# 8x8_led_matrix.net
KiCad netlist of a schematic drawn in EAGLE
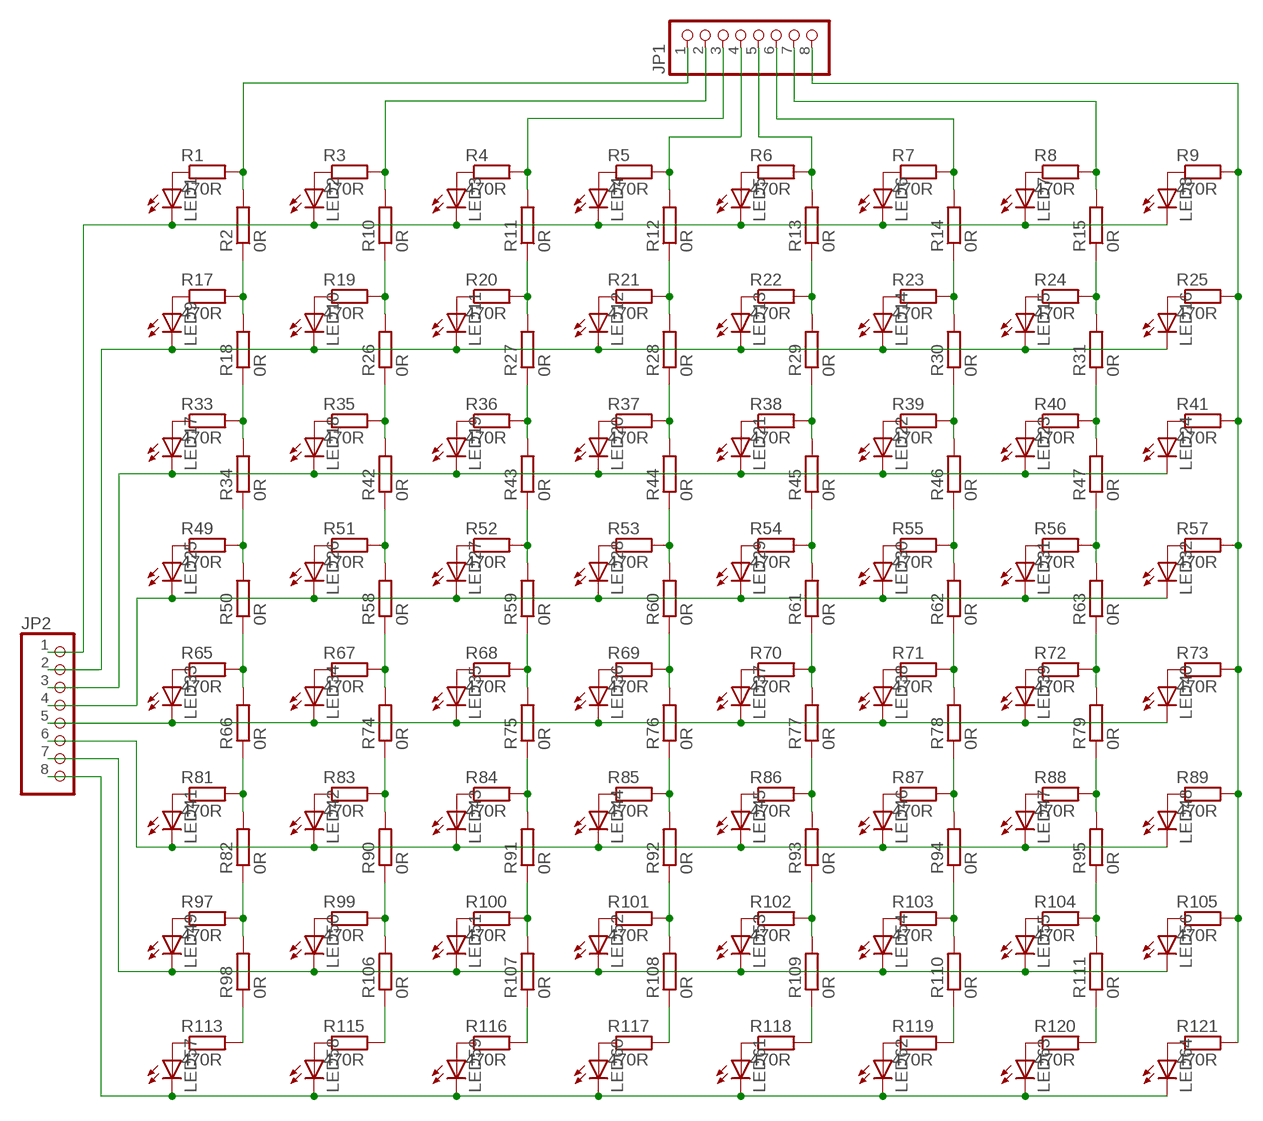
[diagram p0: schematic, sheet 1]

(export (version "E")
  (design (tool "Eeschema 10.0.6"))
  (components
    (comp (ref "JP1")
      (value "PINHD-1X8")
      (footprint "eagle-import:1X08")
      (libsource (lib "eagle-import") (part "PINHD-1X8"))
    )
    (comp (ref "JP2")
      (value "PINHD-1X8")
      (footprint "eagle-import:1X08")
      (libsource (lib "eagle-import") (part "PINHD-1X8"))
    )
    (comp (ref "LED1")
      (value "LED5MM")
      (footprint "eagle-import:LED5MM")
      (libsource (lib "eagle-import") (part "LED5MM"))
    )
    (comp (ref "LED2")
      (value "LED5MM")
      (footprint "eagle-import:LED5MM")
      (libsource (lib "eagle-import") (part "LED5MM"))
    )
    (comp (ref "LED3")
      (value "LED5MM")
      (footprint "eagle-import:LED5MM")
      (libsource (lib "eagle-import") (part "LED5MM"))
    )
    (comp (ref "LED4")
      (value "LED5MM")
      (footprint "eagle-import:LED5MM")
      (libsource (lib "eagle-import") (part "LED5MM"))
    )
    (comp (ref "LED5")
      (value "LED5MM")
      (footprint "eagle-import:LED5MM")
      (libsource (lib "eagle-import") (part "LED5MM"))
    )
    (comp (ref "LED6")
      (value "LED5MM")
      (footprint "eagle-import:LED5MM")
      (libsource (lib "eagle-import") (part "LED5MM"))
    )
    (comp (ref "LED7")
      (value "LED5MM")
      (footprint "eagle-import:LED5MM")
      (libsource (lib "eagle-import") (part "LED5MM"))
    )
    (comp (ref "LED8")
      (value "LED5MM")
      (footprint "eagle-import:LED5MM")
      (libsource (lib "eagle-import") (part "LED5MM"))
    )
    (comp (ref "LED9")
      (value "LED5MM")
      (footprint "eagle-import:LED5MM")
      (libsource (lib "eagle-import") (part "LED5MM"))
    )
    (comp (ref "LED10")
      (value "LED5MM")
      (footprint "eagle-import:LED5MM")
      (libsource (lib "eagle-import") (part "LED5MM"))
    )
    (comp (ref "LED11")
      (value "LED5MM")
      (footprint "eagle-import:LED5MM")
      (libsource (lib "eagle-import") (part "LED5MM"))
    )
    (comp (ref "LED12")
      (value "LED5MM")
      (footprint "eagle-import:LED5MM")
      (libsource (lib "eagle-import") (part "LED5MM"))
    )
    (comp (ref "LED13")
      (value "LED5MM")
      (footprint "eagle-import:LED5MM")
      (libsource (lib "eagle-import") (part "LED5MM"))
    )
    (comp (ref "LED14")
      (value "LED5MM")
      (footprint "eagle-import:LED5MM")
      (libsource (lib "eagle-import") (part "LED5MM"))
    )
    (comp (ref "LED15")
      (value "LED5MM")
      (footprint "eagle-import:LED5MM")
      (libsource (lib "eagle-import") (part "LED5MM"))
    )
    (comp (ref "LED16")
      (value "LED5MM")
      (footprint "eagle-import:LED5MM")
      (libsource (lib "eagle-import") (part "LED5MM"))
    )
    (comp (ref "LED17")
      (value "LED5MM")
      (footprint "eagle-import:LED5MM")
      (libsource (lib "eagle-import") (part "LED5MM"))
    )
    (comp (ref "LED18")
      (value "LED5MM")
      (footprint "eagle-import:LED5MM")
      (libsource (lib "eagle-import") (part "LED5MM"))
    )
    (comp (ref "LED19")
      (value "LED5MM")
      (footprint "eagle-import:LED5MM")
      (libsource (lib "eagle-import") (part "LED5MM"))
    )
    (comp (ref "LED20")
      (value "LED5MM")
      (footprint "eagle-import:LED5MM")
      (libsource (lib "eagle-import") (part "LED5MM"))
    )
    (comp (ref "LED21")
      (value "LED5MM")
      (footprint "eagle-import:LED5MM")
      (libsource (lib "eagle-import") (part "LED5MM"))
    )
    (comp (ref "LED22")
      (value "LED5MM")
      (footprint "eagle-import:LED5MM")
      (libsource (lib "eagle-import") (part "LED5MM"))
    )
    (comp (ref "LED23")
      (value "LED5MM")
      (footprint "eagle-import:LED5MM")
      (libsource (lib "eagle-import") (part "LED5MM"))
    )
    (comp (ref "LED24")
      (value "LED5MM")
      (footprint "eagle-import:LED5MM")
      (libsource (lib "eagle-import") (part "LED5MM"))
    )
    (comp (ref "LED25")
      (value "LED5MM")
      (footprint "eagle-import:LED5MM")
      (libsource (lib "eagle-import") (part "LED5MM"))
    )
    (comp (ref "LED26")
      (value "LED5MM")
      (footprint "eagle-import:LED5MM")
      (libsource (lib "eagle-import") (part "LED5MM"))
    )
    (comp (ref "LED27")
      (value "LED5MM")
      (footprint "eagle-import:LED5MM")
      (libsource (lib "eagle-import") (part "LED5MM"))
    )
    (comp (ref "LED28")
      (value "LED5MM")
      (footprint "eagle-import:LED5MM")
      (libsource (lib "eagle-import") (part "LED5MM"))
    )
    (comp (ref "LED29")
      (value "LED5MM")
      (footprint "eagle-import:LED5MM")
      (libsource (lib "eagle-import") (part "LED5MM"))
    )
    (comp (ref "LED30")
      (value "LED5MM")
      (footprint "eagle-import:LED5MM")
      (libsource (lib "eagle-import") (part "LED5MM"))
    )
    (comp (ref "LED31")
      (value "LED5MM")
      (footprint "eagle-import:LED5MM")
      (libsource (lib "eagle-import") (part "LED5MM"))
    )
    (comp (ref "LED32")
      (value "LED5MM")
      (footprint "eagle-import:LED5MM")
      (libsource (lib "eagle-import") (part "LED5MM"))
    )
    (comp (ref "LED33")
      (value "LED5MM")
      (footprint "eagle-import:LED5MM")
      (libsource (lib "eagle-import") (part "LED5MM"))
    )
    (comp (ref "LED34")
      (value "LED5MM")
      (footprint "eagle-import:LED5MM")
      (libsource (lib "eagle-import") (part "LED5MM"))
    )
    (comp (ref "LED35")
      (value "LED5MM")
      (footprint "eagle-import:LED5MM")
      (libsource (lib "eagle-import") (part "LED5MM"))
    )
    (comp (ref "LED36")
      (value "LED5MM")
      (footprint "eagle-import:LED5MM")
      (libsource (lib "eagle-import") (part "LED5MM"))
    )
    (comp (ref "LED37")
      (value "LED5MM")
      (footprint "eagle-import:LED5MM")
      (libsource (lib "eagle-import") (part "LED5MM"))
    )
    (comp (ref "LED38")
      (value "LED5MM")
      (footprint "eagle-import:LED5MM")
      (libsource (lib "eagle-import") (part "LED5MM"))
    )
    (comp (ref "LED39")
      (value "LED5MM")
      (footprint "eagle-import:LED5MM")
      (libsource (lib "eagle-import") (part "LED5MM"))
    )
    (comp (ref "LED40")
      (value "LED5MM")
      (footprint "eagle-import:LED5MM")
      (libsource (lib "eagle-import") (part "LED5MM"))
    )
    (comp (ref "LED41")
      (value "LED5MM")
      (footprint "eagle-import:LED5MM")
      (libsource (lib "eagle-import") (part "LED5MM"))
    )
    (comp (ref "LED42")
      (value "LED5MM")
      (footprint "eagle-import:LED5MM")
      (libsource (lib "eagle-import") (part "LED5MM"))
    )
    (comp (ref "LED43")
      (value "LED5MM")
      (footprint "eagle-import:LED5MM")
      (libsource (lib "eagle-import") (part "LED5MM"))
    )
    (comp (ref "LED44")
      (value "LED5MM")
      (footprint "eagle-import:LED5MM")
      (libsource (lib "eagle-import") (part "LED5MM"))
    )
    (comp (ref "LED45")
      (value "LED5MM")
      (footprint "eagle-import:LED5MM")
      (libsource (lib "eagle-import") (part "LED5MM"))
    )
    (comp (ref "LED46")
      (value "LED5MM")
      (footprint "eagle-import:LED5MM")
      (libsource (lib "eagle-import") (part "LED5MM"))
    )
    (comp (ref "LED47")
      (value "LED5MM")
      (footprint "eagle-import:LED5MM")
      (libsource (lib "eagle-import") (part "LED5MM"))
    )
    (comp (ref "LED48")
      (value "LED5MM")
      (footprint "eagle-import:LED5MM")
      (libsource (lib "eagle-import") (part "LED5MM"))
    )
    (comp (ref "LED49")
      (value "LED5MM")
      (footprint "eagle-import:LED5MM")
      (libsource (lib "eagle-import") (part "LED5MM"))
    )
    (comp (ref "LED50")
      (value "LED5MM")
      (footprint "eagle-import:LED5MM")
      (libsource (lib "eagle-import") (part "LED5MM"))
    )
    (comp (ref "LED51")
      (value "LED5MM")
      (footprint "eagle-import:LED5MM")
      (libsource (lib "eagle-import") (part "LED5MM"))
    )
    (comp (ref "LED52")
      (value "LED5MM")
      (footprint "eagle-import:LED5MM")
      (libsource (lib "eagle-import") (part "LED5MM"))
    )
    (comp (ref "LED53")
      (value "LED5MM")
      (footprint "eagle-import:LED5MM")
      (libsource (lib "eagle-import") (part "LED5MM"))
    )
    (comp (ref "LED54")
      (value "LED5MM")
      (footprint "eagle-import:LED5MM")
      (libsource (lib "eagle-import") (part "LED5MM"))
    )
    (comp (ref "LED55")
      (value "LED5MM")
      (footprint "eagle-import:LED5MM")
      (libsource (lib "eagle-import") (part "LED5MM"))
    )
    (comp (ref "LED56")
      (value "LED5MM")
      (footprint "eagle-import:LED5MM")
      (libsource (lib "eagle-import") (part "LED5MM"))
    )
    (comp (ref "LED57")
      (value "LED5MM")
      (footprint "eagle-import:LED5MM")
      (libsource (lib "eagle-import") (part "LED5MM"))
    )
    (comp (ref "LED58")
      (value "LED5MM")
      (footprint "eagle-import:LED5MM")
      (libsource (lib "eagle-import") (part "LED5MM"))
    )
    (comp (ref "LED59")
      (value "LED5MM")
      (footprint "eagle-import:LED5MM")
      (libsource (lib "eagle-import") (part "LED5MM"))
    )
    (comp (ref "LED60")
      (value "LED5MM")
      (footprint "eagle-import:LED5MM")
      (libsource (lib "eagle-import") (part "LED5MM"))
    )
    (comp (ref "LED61")
      (value "LED5MM")
      (footprint "eagle-import:LED5MM")
      (libsource (lib "eagle-import") (part "LED5MM"))
    )
    (comp (ref "LED62")
      (value "LED5MM")
      (footprint "eagle-import:LED5MM")
      (libsource (lib "eagle-import") (part "LED5MM"))
    )
    (comp (ref "LED63")
      (value "LED5MM")
      (footprint "eagle-import:LED5MM")
      (libsource (lib "eagle-import") (part "LED5MM"))
    )
    (comp (ref "LED64")
      (value "LED5MM")
      (footprint "eagle-import:LED5MM")
      (libsource (lib "eagle-import") (part "LED5MM"))
    )
    (comp (ref "R1")
      (value "470R")
      (footprint "eagle-import:R0603")
      (libsource (lib "eagle-import") (part "R-EU_R0603"))
    )
    (comp (ref "R2")
      (value "0R")
      (footprint "eagle-import:R1206")
      (libsource (lib "eagle-import") (part "R-EU_R1206"))
    )
    (comp (ref "R3")
      (value "470R")
      (footprint "eagle-import:R0603")
      (libsource (lib "eagle-import") (part "R-EU_R0603"))
    )
    (comp (ref "R4")
      (value "470R")
      (footprint "eagle-import:R0603")
      (libsource (lib "eagle-import") (part "R-EU_R0603"))
    )
    (comp (ref "R5")
      (value "470R")
      (footprint "eagle-import:R0603")
      (libsource (lib "eagle-import") (part "R-EU_R0603"))
    )
    (comp (ref "R6")
      (value "470R")
      (footprint "eagle-import:R0603")
      (libsource (lib "eagle-import") (part "R-EU_R0603"))
    )
    (comp (ref "R7")
      (value "470R")
      (footprint "eagle-import:R0603")
      (libsource (lib "eagle-import") (part "R-EU_R0603"))
    )
    (comp (ref "R8")
      (value "470R")
      (footprint "eagle-import:R0603")
      (libsource (lib "eagle-import") (part "R-EU_R0603"))
    )
    (comp (ref "R9")
      (value "470R")
      (footprint "eagle-import:R0603")
      (libsource (lib "eagle-import") (part "R-EU_R0603"))
    )
    (comp (ref "R10")
      (value "0R")
      (footprint "eagle-import:R1206")
      (libsource (lib "eagle-import") (part "R-EU_R1206"))
    )
    (comp (ref "R11")
      (value "0R")
      (footprint "eagle-import:R1206")
      (libsource (lib "eagle-import") (part "R-EU_R1206"))
    )
    (comp (ref "R12")
      (value "0R")
      (footprint "eagle-import:R1206")
      (libsource (lib "eagle-import") (part "R-EU_R1206"))
    )
    (comp (ref "R13")
      (value "0R")
      (footprint "eagle-import:R1206")
      (libsource (lib "eagle-import") (part "R-EU_R1206"))
    )
    (comp (ref "R14")
      (value "0R")
      (footprint "eagle-import:R1206")
      (libsource (lib "eagle-import") (part "R-EU_R1206"))
    )
    (comp (ref "R15")
      (value "0R")
      (footprint "eagle-import:R1206")
      (libsource (lib "eagle-import") (part "R-EU_R1206"))
    )
    (comp (ref "R17")
      (value "470R")
      (footprint "eagle-import:R0603")
      (libsource (lib "eagle-import") (part "R-EU_R0603"))
    )
    (comp (ref "R18")
      (value "0R")
      (footprint "eagle-import:R1206")
      (libsource (lib "eagle-import") (part "R-EU_R1206"))
    )
    (comp (ref "R19")
      (value "470R")
      (footprint "eagle-import:R0603")
      (libsource (lib "eagle-import") (part "R-EU_R0603"))
    )
    (comp (ref "R20")
      (value "470R")
      (footprint "eagle-import:R0603")
      (libsource (lib "eagle-import") (part "R-EU_R0603"))
    )
    (comp (ref "R21")
      (value "470R")
      (footprint "eagle-import:R0603")
      (libsource (lib "eagle-import") (part "R-EU_R0603"))
    )
    (comp (ref "R22")
      (value "470R")
      (footprint "eagle-import:R0603")
      (libsource (lib "eagle-import") (part "R-EU_R0603"))
    )
    (comp (ref "R23")
      (value "470R")
      (footprint "eagle-import:R0603")
      (libsource (lib "eagle-import") (part "R-EU_R0603"))
    )
    (comp (ref "R24")
      (value "470R")
      (footprint "eagle-import:R0603")
      (libsource (lib "eagle-import") (part "R-EU_R0603"))
    )
    (comp (ref "R25")
      (value "470R")
      (footprint "eagle-import:R0603")
      (libsource (lib "eagle-import") (part "R-EU_R0603"))
    )
    (comp (ref "R26")
      (value "0R")
      (footprint "eagle-import:R1206")
      (libsource (lib "eagle-import") (part "R-EU_R1206"))
    )
    (comp (ref "R27")
      (value "0R")
      (footprint "eagle-import:R1206")
      (libsource (lib "eagle-import") (part "R-EU_R1206"))
    )
    (comp (ref "R28")
      (value "0R")
      (footprint "eagle-import:R1206")
      (libsource (lib "eagle-import") (part "R-EU_R1206"))
    )
    (comp (ref "R29")
      (value "0R")
      (footprint "eagle-import:R1206")
      (libsource (lib "eagle-import") (part "R-EU_R1206"))
    )
    (comp (ref "R30")
      (value "0R")
      (footprint "eagle-import:R1206")
      (libsource (lib "eagle-import") (part "R-EU_R1206"))
    )
    (comp (ref "R31")
      (value "0R")
      (footprint "eagle-import:R1206")
      (libsource (lib "eagle-import") (part "R-EU_R1206"))
    )
    (comp (ref "R33")
      (value "470R")
      (footprint "eagle-import:R0603")
      (libsource (lib "eagle-import") (part "R-EU_R0603"))
    )
    (comp (ref "R34")
      (value "0R")
      (footprint "eagle-import:R1206")
      (libsource (lib "eagle-import") (part "R-EU_R1206"))
    )
    (comp (ref "R35")
      (value "470R")
      (footprint "eagle-import:R0603")
      (libsource (lib "eagle-import") (part "R-EU_R0603"))
    )
    (comp (ref "R36")
      (value "470R")
      (footprint "eagle-import:R0603")
      (libsource (lib "eagle-import") (part "R-EU_R0603"))
    )
    (comp (ref "R37")
      (value "470R")
      (footprint "eagle-import:R0603")
      (libsource (lib "eagle-import") (part "R-EU_R0603"))
    )
    (comp (ref "R38")
      (value "470R")
      (footprint "eagle-import:R0603")
      (libsource (lib "eagle-import") (part "R-EU_R0603"))
    )
    (comp (ref "R39")
      (value "470R")
      (footprint "eagle-import:R0603")
      (libsource (lib "eagle-import") (part "R-EU_R0603"))
    )
    (comp (ref "R40")
      (value "470R")
      (footprint "eagle-import:R0603")
      (libsource (lib "eagle-import") (part "R-EU_R0603"))
    )
    (comp (ref "R41")
      (value "470R")
      (footprint "eagle-import:R0603")
      (libsource (lib "eagle-import") (part "R-EU_R0603"))
    )
    (comp (ref "R42")
      (value "0R")
      (footprint "eagle-import:R1206")
      (libsource (lib "eagle-import") (part "R-EU_R1206"))
    )
    (comp (ref "R43")
      (value "0R")
      (footprint "eagle-import:R1206")
      (libsource (lib "eagle-import") (part "R-EU_R1206"))
    )
    (comp (ref "R44")
      (value "0R")
      (footprint "eagle-import:R1206")
      (libsource (lib "eagle-import") (part "R-EU_R1206"))
    )
    (comp (ref "R45")
      (value "0R")
      (footprint "eagle-import:R1206")
      (libsource (lib "eagle-import") (part "R-EU_R1206"))
    )
    (comp (ref "R46")
      (value "0R")
      (footprint "eagle-import:R1206")
      (libsource (lib "eagle-import") (part "R-EU_R1206"))
    )
    (comp (ref "R47")
      (value "0R")
      (footprint "eagle-import:R1206")
      (libsource (lib "eagle-import") (part "R-EU_R1206"))
    )
    (comp (ref "R49")
      (value "470R")
      (footprint "eagle-import:R0603")
      (libsource (lib "eagle-import") (part "R-EU_R0603"))
    )
    (comp (ref "R50")
      (value "0R")
      (footprint "eagle-import:R1206")
      (libsource (lib "eagle-import") (part "R-EU_R1206"))
    )
    (comp (ref "R51")
      (value "470R")
      (footprint "eagle-import:R0603")
      (libsource (lib "eagle-import") (part "R-EU_R0603"))
    )
    (comp (ref "R52")
      (value "470R")
      (footprint "eagle-import:R0603")
      (libsource (lib "eagle-import") (part "R-EU_R0603"))
    )
    (comp (ref "R53")
      (value "470R")
      (footprint "eagle-import:R0603")
      (libsource (lib "eagle-import") (part "R-EU_R0603"))
    )
    (comp (ref "R54")
      (value "470R")
      (footprint "eagle-import:R0603")
      (libsource (lib "eagle-import") (part "R-EU_R0603"))
    )
    (comp (ref "R55")
      (value "470R")
      (footprint "eagle-import:R0603")
      (libsource (lib "eagle-import") (part "R-EU_R0603"))
    )
    (comp (ref "R56")
      (value "470R")
      (footprint "eagle-import:R0603")
      (libsource (lib "eagle-import") (part "R-EU_R0603"))
    )
    (comp (ref "R57")
      (value "470R")
      (footprint "eagle-import:R0603")
      (libsource (lib "eagle-import") (part "R-EU_R0603"))
    )
    (comp (ref "R58")
      (value "0R")
      (footprint "eagle-import:R1206")
      (libsource (lib "eagle-import") (part "R-EU_R1206"))
    )
    (comp (ref "R59")
      (value "0R")
      (footprint "eagle-import:R1206")
      (libsource (lib "eagle-import") (part "R-EU_R1206"))
    )
    (comp (ref "R60")
      (value "0R")
      (footprint "eagle-import:R1206")
      (libsource (lib "eagle-import") (part "R-EU_R1206"))
    )
    (comp (ref "R61")
      (value "0R")
      (footprint "eagle-import:R1206")
      (libsource (lib "eagle-import") (part "R-EU_R1206"))
    )
    (comp (ref "R62")
      (value "0R")
      (footprint "eagle-import:R1206")
      (libsource (lib "eagle-import") (part "R-EU_R1206"))
    )
    (comp (ref "R63")
      (value "0R")
      (footprint "eagle-import:R1206")
      (libsource (lib "eagle-import") (part "R-EU_R1206"))
    )
    (comp (ref "R65")
      (value "470R")
      (footprint "eagle-import:R0603")
      (libsource (lib "eagle-import") (part "R-EU_R0603"))
    )
    (comp (ref "R66")
      (value "0R")
      (footprint "eagle-import:R1206")
      (libsource (lib "eagle-import") (part "R-EU_R1206"))
    )
    (comp (ref "R67")
      (value "470R")
      (footprint "eagle-import:R0603")
      (libsource (lib "eagle-import") (part "R-EU_R0603"))
    )
    (comp (ref "R68")
      (value "470R")
      (footprint "eagle-import:R0603")
      (libsource (lib "eagle-import") (part "R-EU_R0603"))
    )
    (comp (ref "R69")
      (value "470R")
      (footprint "eagle-import:R0603")
      (libsource (lib "eagle-import") (part "R-EU_R0603"))
    )
    (comp (ref "R70")
      (value "470R")
      (footprint "eagle-import:R0603")
      (libsource (lib "eagle-import") (part "R-EU_R0603"))
    )
    (comp (ref "R71")
      (value "470R")
      (footprint "eagle-import:R0603")
      (libsource (lib "eagle-import") (part "R-EU_R0603"))
    )
    (comp (ref "R72")
      (value "470R")
      (footprint "eagle-import:R0603")
      (libsource (lib "eagle-import") (part "R-EU_R0603"))
    )
    (comp (ref "R73")
      (value "470R")
      (footprint "eagle-import:R0603")
      (libsource (lib "eagle-import") (part "R-EU_R0603"))
    )
    (comp (ref "R74")
      (value "0R")
      (footprint "eagle-import:R1206")
      (libsource (lib "eagle-import") (part "R-EU_R1206"))
    )
    (comp (ref "R75")
      (value "0R")
      (footprint "eagle-import:R1206")
      (libsource (lib "eagle-import") (part "R-EU_R1206"))
    )
    (comp (ref "R76")
      (value "0R")
      (footprint "eagle-import:R1206")
      (libsource (lib "eagle-import") (part "R-EU_R1206"))
    )
    (comp (ref "R77")
      (value "0R")
      (footprint "eagle-import:R1206")
      (libsource (lib "eagle-import") (part "R-EU_R1206"))
    )
    (comp (ref "R78")
      (value "0R")
      (footprint "eagle-import:R1206")
      (libsource (lib "eagle-import") (part "R-EU_R1206"))
    )
    (comp (ref "R79")
      (value "0R")
      (footprint "eagle-import:R1206")
      (libsource (lib "eagle-import") (part "R-EU_R1206"))
    )
    (comp (ref "R81")
      (value "470R")
      (footprint "eagle-import:R0603")
      (libsource (lib "eagle-import") (part "R-EU_R0603"))
    )
    (comp (ref "R82")
      (value "0R")
      (footprint "eagle-import:R1206")
      (libsource (lib "eagle-import") (part "R-EU_R1206"))
    )
    (comp (ref "R83")
      (value "470R")
      (footprint "eagle-import:R0603")
      (libsource (lib "eagle-import") (part "R-EU_R0603"))
    )
    (comp (ref "R84")
      (value "470R")
      (footprint "eagle-import:R0603")
      (libsource (lib "eagle-import") (part "R-EU_R0603"))
    )
    (comp (ref "R85")
      (value "470R")
      (footprint "eagle-import:R0603")
      (libsource (lib "eagle-import") (part "R-EU_R0603"))
    )
    (comp (ref "R86")
      (value "470R")
      (footprint "eagle-import:R0603")
      (libsource (lib "eagle-import") (part "R-EU_R0603"))
    )
    (comp (ref "R87")
      (value "470R")
      (footprint "eagle-import:R0603")
      (libsource (lib "eagle-import") (part "R-EU_R0603"))
    )
    (comp (ref "R88")
      (value "470R")
      (footprint "eagle-import:R0603")
      (libsource (lib "eagle-import") (part "R-EU_R0603"))
    )
    (comp (ref "R89")
      (value "470R")
      (footprint "eagle-import:R0603")
      (libsource (lib "eagle-import") (part "R-EU_R0603"))
    )
    (comp (ref "R90")
      (value "0R")
      (footprint "eagle-import:R1206")
      (libsource (lib "eagle-import") (part "R-EU_R1206"))
    )
    (comp (ref "R91")
      (value "0R")
      (footprint "eagle-import:R1206")
      (libsource (lib "eagle-import") (part "R-EU_R1206"))
    )
    (comp (ref "R92")
      (value "0R")
      (footprint "eagle-import:R1206")
      (libsource (lib "eagle-import") (part "R-EU_R1206"))
    )
    (comp (ref "R93")
      (value "0R")
      (footprint "eagle-import:R1206")
      (libsource (lib "eagle-import") (part "R-EU_R1206"))
    )
    (comp (ref "R94")
      (value "0R")
      (footprint "eagle-import:R1206")
      (libsource (lib "eagle-import") (part "R-EU_R1206"))
    )
    (comp (ref "R95")
      (value "0R")
      (footprint "eagle-import:R1206")
      (libsource (lib "eagle-import") (part "R-EU_R1206"))
    )
    (comp (ref "R97")
      (value "470R")
      (footprint "eagle-import:R0603")
      (libsource (lib "eagle-import") (part "R-EU_R0603"))
    )
    (comp (ref "R98")
      (value "0R")
      (footprint "eagle-import:R1206")
      (libsource (lib "eagle-import") (part "R-EU_R1206"))
    )
    (comp (ref "R99")
      (value "470R")
      (footprint "eagle-import:R0603")
      (libsource (lib "eagle-import") (part "R-EU_R0603"))
    )
    (comp (ref "R100")
      (value "470R")
      (footprint "eagle-import:R0603")
      (libsource (lib "eagle-import") (part "R-EU_R0603"))
    )
    (comp (ref "R101")
      (value "470R")
      (footprint "eagle-import:R0603")
      (libsource (lib "eagle-import") (part "R-EU_R0603"))
    )
    (comp (ref "R102")
      (value "470R")
      (footprint "eagle-import:R0603")
      (libsource (lib "eagle-import") (part "R-EU_R0603"))
    )
    (comp (ref "R103")
      (value "470R")
      (footprint "eagle-import:R0603")
      (libsource (lib "eagle-import") (part "R-EU_R0603"))
    )
    (comp (ref "R104")
      (value "470R")
      (footprint "eagle-import:R0603")
      (libsource (lib "eagle-import") (part "R-EU_R0603"))
    )
    (comp (ref "R105")
      (value "470R")
      (footprint "eagle-import:R0603")
      (libsource (lib "eagle-import") (part "R-EU_R0603"))
    )
    (comp (ref "R106")
      (value "0R")
      (footprint "eagle-import:R1206")
      (libsource (lib "eagle-import") (part "R-EU_R1206"))
    )
    (comp (ref "R107")
      (value "0R")
      (footprint "eagle-import:R1206")
      (libsource (lib "eagle-import") (part "R-EU_R1206"))
    )
    (comp (ref "R108")
      (value "0R")
      (footprint "eagle-import:R1206")
      (libsource (lib "eagle-import") (part "R-EU_R1206"))
    )
    (comp (ref "R109")
      (value "0R")
      (footprint "eagle-import:R1206")
      (libsource (lib "eagle-import") (part "R-EU_R1206"))
    )
    (comp (ref "R110")
      (value "0R")
      (footprint "eagle-import:R1206")
      (libsource (lib "eagle-import") (part "R-EU_R1206"))
    )
    (comp (ref "R111")
      (value "0R")
      (footprint "eagle-import:R1206")
      (libsource (lib "eagle-import") (part "R-EU_R1206"))
    )
    (comp (ref "R113")
      (value "470R")
      (footprint "eagle-import:R0603")
      (libsource (lib "eagle-import") (part "R-EU_R0603"))
    )
    (comp (ref "R115")
      (value "470R")
      (footprint "eagle-import:R0603")
      (libsource (lib "eagle-import") (part "R-EU_R0603"))
    )
    (comp (ref "R116")
      (value "470R")
      (footprint "eagle-import:R0603")
      (libsource (lib "eagle-import") (part "R-EU_R0603"))
    )
    (comp (ref "R117")
      (value "470R")
      (footprint "eagle-import:R0603")
      (libsource (lib "eagle-import") (part "R-EU_R0603"))
    )
    (comp (ref "R118")
      (value "470R")
      (footprint "eagle-import:R0603")
      (libsource (lib "eagle-import") (part "R-EU_R0603"))
    )
    (comp (ref "R119")
      (value "470R")
      (footprint "eagle-import:R0603")
      (libsource (lib "eagle-import") (part "R-EU_R0603"))
    )
    (comp (ref "R120")
      (value "470R")
      (footprint "eagle-import:R0603")
      (libsource (lib "eagle-import") (part "R-EU_R0603"))
    )
    (comp (ref "R121")
      (value "470R")
      (footprint "eagle-import:R0603")
      (libsource (lib "eagle-import") (part "R-EU_R0603"))
    )
  )
  (nets
    (net (code "1") (name "Net-(JP1-Pad1)") (class "Default")
      (node (ref "JP1") (pin "1") (pinfunction "1_1") (pintype "passive"))
      (node (ref "R1") (pin "2") (pinfunction "2_2") (pintype "passive"))
      (node (ref "R2") (pin "2") (pinfunction "2_2") (pintype "passive"))
    )
    (net (code "2") (name "Net-(JP1-Pad2)") (class "Default")
      (node (ref "JP1") (pin "2") (pinfunction "2_2") (pintype "passive"))
      (node (ref "R10") (pin "2") (pinfunction "2_2") (pintype "passive"))
      (node (ref "R3") (pin "2") (pinfunction "2_2") (pintype "passive"))
    )
    (net (code "3") (name "Net-(JP1-Pad3)") (class "Default")
      (node (ref "JP1") (pin "3") (pinfunction "3_3") (pintype "passive"))
      (node (ref "R11") (pin "2") (pinfunction "2_2") (pintype "passive"))
      (node (ref "R4") (pin "2") (pinfunction "2_2") (pintype "passive"))
    )
    (net (code "4") (name "Net-(JP1-Pad4)") (class "Default")
      (node (ref "JP1") (pin "4") (pinfunction "4_4") (pintype "passive"))
      (node (ref "R12") (pin "2") (pinfunction "2_2") (pintype "passive"))
      (node (ref "R5") (pin "2") (pinfunction "2_2") (pintype "passive"))
    )
    (net (code "5") (name "Net-(JP1-Pad5)") (class "Default")
      (node (ref "JP1") (pin "5") (pinfunction "5_5") (pintype "passive"))
      (node (ref "R13") (pin "2") (pinfunction "2_2") (pintype "passive"))
      (node (ref "R6") (pin "2") (pinfunction "2_2") (pintype "passive"))
    )
    (net (code "6") (name "Net-(JP1-Pad6)") (class "Default")
      (node (ref "JP1") (pin "6") (pinfunction "6_6") (pintype "passive"))
      (node (ref "R14") (pin "2") (pinfunction "2_2") (pintype "passive"))
      (node (ref "R7") (pin "2") (pinfunction "2_2") (pintype "passive"))
    )
    (net (code "7") (name "Net-(JP1-Pad7)") (class "Default")
      (node (ref "JP1") (pin "7") (pinfunction "7_7") (pintype "passive"))
      (node (ref "R15") (pin "2") (pinfunction "2_2") (pintype "passive"))
      (node (ref "R8") (pin "2") (pinfunction "2_2") (pintype "passive"))
    )
    (net (code "8") (name "Net-(JP1-Pad8)") (class "Default")
      (node (ref "JP1") (pin "8") (pinfunction "8_8") (pintype "passive"))
      (node (ref "R105") (pin "2") (pinfunction "2_2") (pintype "passive"))
      (node (ref "R121") (pin "2") (pinfunction "2_2") (pintype "passive"))
      (node (ref "R25") (pin "2") (pinfunction "2_2") (pintype "passive"))
      (node (ref "R41") (pin "2") (pinfunction "2_2") (pintype "passive"))
      (node (ref "R57") (pin "2") (pinfunction "2_2") (pintype "passive"))
      (node (ref "R73") (pin "2") (pinfunction "2_2") (pintype "passive"))
      (node (ref "R89") (pin "2") (pinfunction "2_2") (pintype "passive"))
      (node (ref "R9") (pin "2") (pinfunction "2_2") (pintype "passive"))
    )
    (net (code "9") (name "Net-(LED1-C)") (class "Default")
      (node (ref "JP2") (pin "1") (pinfunction "1_1") (pintype "passive"))
      (node (ref "LED1") (pin "K") (pinfunction "C_K") (pintype "passive"))
      (node (ref "LED2") (pin "K") (pinfunction "C_K") (pintype "passive"))
      (node (ref "LED3") (pin "K") (pinfunction "C_K") (pintype "passive"))
      (node (ref "LED4") (pin "K") (pinfunction "C_K") (pintype "passive"))
      (node (ref "LED5") (pin "K") (pinfunction "C_K") (pintype "passive"))
      (node (ref "LED6") (pin "K") (pinfunction "C_K") (pintype "passive"))
      (node (ref "LED7") (pin "K") (pinfunction "C_K") (pintype "passive"))
      (node (ref "LED8") (pin "K") (pinfunction "C_K") (pintype "passive"))
    )
    (net (code "10") (name "Net-(LED1-PadA)") (class "Default")
      (node (ref "LED1") (pin "A") (pinfunction "A_A") (pintype "passive"))
      (node (ref "R1") (pin "1") (pinfunction "1_1") (pintype "passive"))
    )
    (net (code "11") (name "Net-(LED2-PadA)") (class "Default")
      (node (ref "LED2") (pin "A") (pinfunction "A_A") (pintype "passive"))
      (node (ref "R3") (pin "1") (pinfunction "1_1") (pintype "passive"))
    )
    (net (code "12") (name "Net-(LED3-PadA)") (class "Default")
      (node (ref "LED3") (pin "A") (pinfunction "A_A") (pintype "passive"))
      (node (ref "R4") (pin "1") (pinfunction "1_1") (pintype "passive"))
    )
    (net (code "13") (name "Net-(LED4-PadA)") (class "Default")
      (node (ref "LED4") (pin "A") (pinfunction "A_A") (pintype "passive"))
      (node (ref "R5") (pin "1") (pinfunction "1_1") (pintype "passive"))
    )
    (net (code "14") (name "Net-(LED5-PadA)") (class "Default")
      (node (ref "LED5") (pin "A") (pinfunction "A_A") (pintype "passive"))
      (node (ref "R6") (pin "1") (pinfunction "1_1") (pintype "passive"))
    )
    (net (code "15") (name "Net-(LED6-PadA)") (class "Default")
      (node (ref "LED6") (pin "A") (pinfunction "A_A") (pintype "passive"))
      (node (ref "R7") (pin "1") (pinfunction "1_1") (pintype "passive"))
    )
    (net (code "16") (name "Net-(LED7-PadA)") (class "Default")
      (node (ref "LED7") (pin "A") (pinfunction "A_A") (pintype "passive"))
      (node (ref "R8") (pin "1") (pinfunction "1_1") (pintype "passive"))
    )
    (net (code "17") (name "Net-(LED8-PadA)") (class "Default")
      (node (ref "LED8") (pin "A") (pinfunction "A_A") (pintype "passive"))
      (node (ref "R9") (pin "1") (pinfunction "1_1") (pintype "passive"))
    )
    (net (code "18") (name "Net-(LED9-PadA)") (class "Default")
      (node (ref "LED9") (pin "A") (pinfunction "A_A") (pintype "passive"))
      (node (ref "R17") (pin "1") (pinfunction "1_1") (pintype "passive"))
    )
    (net (code "19") (name "Net-(LED10-C)") (class "Default")
      (node (ref "JP2") (pin "2") (pinfunction "2_2") (pintype "passive"))
      (node (ref "LED10") (pin "K") (pinfunction "C_K") (pintype "passive"))
      (node (ref "LED11") (pin "K") (pinfunction "C_K") (pintype "passive"))
      (node (ref "LED12") (pin "K") (pinfunction "C_K") (pintype "passive"))
      (node (ref "LED13") (pin "K") (pinfunction "C_K") (pintype "passive"))
      (node (ref "LED14") (pin "K") (pinfunction "C_K") (pintype "passive"))
      (node (ref "LED15") (pin "K") (pinfunction "C_K") (pintype "passive"))
      (node (ref "LED16") (pin "K") (pinfunction "C_K") (pintype "passive"))
      (node (ref "LED9") (pin "K") (pinfunction "C_K") (pintype "passive"))
    )
    (net (code "20") (name "Net-(LED10-PadA)") (class "Default")
      (node (ref "LED10") (pin "A") (pinfunction "A_A") (pintype "passive"))
      (node (ref "R19") (pin "1") (pinfunction "1_1") (pintype "passive"))
    )
    (net (code "21") (name "Net-(LED11-PadA)") (class "Default")
      (node (ref "LED11") (pin "A") (pinfunction "A_A") (pintype "passive"))
      (node (ref "R20") (pin "1") (pinfunction "1_1") (pintype "passive"))
    )
    (net (code "22") (name "Net-(LED12-PadA)") (class "Default")
      (node (ref "LED12") (pin "A") (pinfunction "A_A") (pintype "passive"))
      (node (ref "R21") (pin "1") (pinfunction "1_1") (pintype "passive"))
    )
    (net (code "23") (name "Net-(LED13-PadA)") (class "Default")
      (node (ref "LED13") (pin "A") (pinfunction "A_A") (pintype "passive"))
      (node (ref "R22") (pin "1") (pinfunction "1_1") (pintype "passive"))
    )
    (net (code "24") (name "Net-(LED14-PadA)") (class "Default")
      (node (ref "LED14") (pin "A") (pinfunction "A_A") (pintype "passive"))
      (node (ref "R23") (pin "1") (pinfunction "1_1") (pintype "passive"))
    )
    (net (code "25") (name "Net-(LED15-PadA)") (class "Default")
      (node (ref "LED15") (pin "A") (pinfunction "A_A") (pintype "passive"))
      (node (ref "R24") (pin "1") (pinfunction "1_1") (pintype "passive"))
    )
    (net (code "26") (name "Net-(LED16-PadA)") (class "Default")
      (node (ref "LED16") (pin "A") (pinfunction "A_A") (pintype "passive"))
      (node (ref "R25") (pin "1") (pinfunction "1_1") (pintype "passive"))
    )
    (net (code "27") (name "Net-(LED17-C)") (class "Default")
      (node (ref "JP2") (pin "3") (pinfunction "3_3") (pintype "passive"))
      (node (ref "LED17") (pin "K") (pinfunction "C_K") (pintype "passive"))
      (node (ref "LED18") (pin "K") (pinfunction "C_K") (pintype "passive"))
      (node (ref "LED19") (pin "K") (pinfunction "C_K") (pintype "passive"))
      (node (ref "LED20") (pin "K") (pinfunction "C_K") (pintype "passive"))
      (node (ref "LED21") (pin "K") (pinfunction "C_K") (pintype "passive"))
      (node (ref "LED22") (pin "K") (pinfunction "C_K") (pintype "passive"))
      (node (ref "LED23") (pin "K") (pinfunction "C_K") (pintype "passive"))
      (node (ref "LED24") (pin "K") (pinfunction "C_K") (pintype "passive"))
    )
    (net (code "28") (name "Net-(LED17-PadA)") (class "Default")
      (node (ref "LED17") (pin "A") (pinfunction "A_A") (pintype "passive"))
      (node (ref "R33") (pin "1") (pinfunction "1_1") (pintype "passive"))
    )
    (net (code "29") (name "Net-(LED18-PadA)") (class "Default")
      (node (ref "LED18") (pin "A") (pinfunction "A_A") (pintype "passive"))
      (node (ref "R35") (pin "1") (pinfunction "1_1") (pintype "passive"))
    )
    (net (code "30") (name "Net-(LED19-PadA)") (class "Default")
      (node (ref "LED19") (pin "A") (pinfunction "A_A") (pintype "passive"))
      (node (ref "R36") (pin "1") (pinfunction "1_1") (pintype "passive"))
    )
    (net (code "31") (name "Net-(LED20-PadA)") (class "Default")
      (node (ref "LED20") (pin "A") (pinfunction "A_A") (pintype "passive"))
      (node (ref "R37") (pin "1") (pinfunction "1_1") (pintype "passive"))
    )
    (net (code "32") (name "Net-(LED21-PadA)") (class "Default")
      (node (ref "LED21") (pin "A") (pinfunction "A_A") (pintype "passive"))
      (node (ref "R38") (pin "1") (pinfunction "1_1") (pintype "passive"))
    )
    (net (code "33") (name "Net-(LED22-PadA)") (class "Default")
      (node (ref "LED22") (pin "A") (pinfunction "A_A") (pintype "passive"))
      (node (ref "R39") (pin "1") (pinfunction "1_1") (pintype "passive"))
    )
    (net (code "34") (name "Net-(LED23-PadA)") (class "Default")
      (node (ref "LED23") (pin "A") (pinfunction "A_A") (pintype "passive"))
      (node (ref "R40") (pin "1") (pinfunction "1_1") (pintype "passive"))
    )
    (net (code "35") (name "Net-(LED24-PadA)") (class "Default")
      (node (ref "LED24") (pin "A") (pinfunction "A_A") (pintype "passive"))
      (node (ref "R41") (pin "1") (pinfunction "1_1") (pintype "passive"))
    )
    (net (code "36") (name "Net-(LED25-C)") (class "Default")
      (node (ref "JP2") (pin "4") (pinfunction "4_4") (pintype "passive"))
      (node (ref "LED25") (pin "K") (pinfunction "C_K") (pintype "passive"))
      (node (ref "LED26") (pin "K") (pinfunction "C_K") (pintype "passive"))
      (node (ref "LED27") (pin "K") (pinfunction "C_K") (pintype "passive"))
      (node (ref "LED28") (pin "K") (pinfunction "C_K") (pintype "passive"))
      (node (ref "LED29") (pin "K") (pinfunction "C_K") (pintype "passive"))
      (node (ref "LED30") (pin "K") (pinfunction "C_K") (pintype "passive"))
      (node (ref "LED31") (pin "K") (pinfunction "C_K") (pintype "passive"))
      (node (ref "LED32") (pin "K") (pinfunction "C_K") (pintype "passive"))
    )
    (net (code "37") (name "Net-(LED25-PadA)") (class "Default")
      (node (ref "LED25") (pin "A") (pinfunction "A_A") (pintype "passive"))
      (node (ref "R49") (pin "1") (pinfunction "1_1") (pintype "passive"))
    )
    (net (code "38") (name "Net-(LED26-PadA)") (class "Default")
      (node (ref "LED26") (pin "A") (pinfunction "A_A") (pintype "passive"))
      (node (ref "R51") (pin "1") (pinfunction "1_1") (pintype "passive"))
    )
    (net (code "39") (name "Net-(LED27-PadA)") (class "Default")
      (node (ref "LED27") (pin "A") (pinfunction "A_A") (pintype "passive"))
      (node (ref "R52") (pin "1") (pinfunction "1_1") (pintype "passive"))
    )
    (net (code "40") (name "Net-(LED28-PadA)") (class "Default")
      (node (ref "LED28") (pin "A") (pinfunction "A_A") (pintype "passive"))
      (node (ref "R53") (pin "1") (pinfunction "1_1") (pintype "passive"))
    )
    (net (code "41") (name "Net-(LED29-PadA)") (class "Default")
      (node (ref "LED29") (pin "A") (pinfunction "A_A") (pintype "passive"))
      (node (ref "R54") (pin "1") (pinfunction "1_1") (pintype "passive"))
    )
    (net (code "42") (name "Net-(LED30-PadA)") (class "Default")
      (node (ref "LED30") (pin "A") (pinfunction "A_A") (pintype "passive"))
      (node (ref "R55") (pin "1") (pinfunction "1_1") (pintype "passive"))
    )
    (net (code "43") (name "Net-(LED31-PadA)") (class "Default")
      (node (ref "LED31") (pin "A") (pinfunction "A_A") (pintype "passive"))
      (node (ref "R56") (pin "1") (pinfunction "1_1") (pintype "passive"))
    )
    (net (code "44") (name "Net-(LED32-PadA)") (class "Default")
      (node (ref "LED32") (pin "A") (pinfunction "A_A") (pintype "passive"))
      (node (ref "R57") (pin "1") (pinfunction "1_1") (pintype "passive"))
    )
    (net (code "45") (name "Net-(LED33-C)") (class "Default")
      (node (ref "JP2") (pin "5") (pinfunction "5_5") (pintype "passive"))
      (node (ref "LED33") (pin "K") (pinfunction "C_K") (pintype "passive"))
      (node (ref "LED34") (pin "K") (pinfunction "C_K") (pintype "passive"))
      (node (ref "LED35") (pin "K") (pinfunction "C_K") (pintype "passive"))
      (node (ref "LED36") (pin "K") (pinfunction "C_K") (pintype "passive"))
      (node (ref "LED37") (pin "K") (pinfunction "C_K") (pintype "passive"))
      (node (ref "LED38") (pin "K") (pinfunction "C_K") (pintype "passive"))
      (node (ref "LED39") (pin "K") (pinfunction "C_K") (pintype "passive"))
      (node (ref "LED40") (pin "K") (pinfunction "C_K") (pintype "passive"))
    )
    (net (code "46") (name "Net-(LED33-PadA)") (class "Default")
      (node (ref "LED33") (pin "A") (pinfunction "A_A") (pintype "passive"))
      (node (ref "R65") (pin "1") (pinfunction "1_1") (pintype "passive"))
    )
    (net (code "47") (name "Net-(LED34-PadA)") (class "Default")
      (node (ref "LED34") (pin "A") (pinfunction "A_A") (pintype "passive"))
      (node (ref "R67") (pin "1") (pinfunction "1_1") (pintype "passive"))
    )
    (net (code "48") (name "Net-(LED35-PadA)") (class "Default")
      (node (ref "LED35") (pin "A") (pinfunction "A_A") (pintype "passive"))
      (node (ref "R68") (pin "1") (pinfunction "1_1") (pintype "passive"))
    )
    (net (code "49") (name "Net-(LED36-PadA)") (class "Default")
      (node (ref "LED36") (pin "A") (pinfunction "A_A") (pintype "passive"))
      (node (ref "R69") (pin "1") (pinfunction "1_1") (pintype "passive"))
    )
    (net (code "50") (name "Net-(LED37-PadA)") (class "Default")
      (node (ref "LED37") (pin "A") (pinfunction "A_A") (pintype "passive"))
      (node (ref "R70") (pin "1") (pinfunction "1_1") (pintype "passive"))
    )
    (net (code "51") (name "Net-(LED38-PadA)") (class "Default")
      (node (ref "LED38") (pin "A") (pinfunction "A_A") (pintype "passive"))
      (node (ref "R71") (pin "1") (pinfunction "1_1") (pintype "passive"))
    )
    (net (code "52") (name "Net-(LED39-PadA)") (class "Default")
      (node (ref "LED39") (pin "A") (pinfunction "A_A") (pintype "passive"))
      (node (ref "R72") (pin "1") (pinfunction "1_1") (pintype "passive"))
    )
    (net (code "53") (name "Net-(LED40-PadA)") (class "Default")
      (node (ref "LED40") (pin "A") (pinfunction "A_A") (pintype "passive"))
      (node (ref "R73") (pin "1") (pinfunction "1_1") (pintype "passive"))
    )
    (net (code "54") (name "Net-(LED41-C)") (class "Default")
      (node (ref "JP2") (pin "6") (pinfunction "6_6") (pintype "passive"))
      (node (ref "LED41") (pin "K") (pinfunction "C_K") (pintype "passive"))
      (node (ref "LED42") (pin "K") (pinfunction "C_K") (pintype "passive"))
      (node (ref "LED43") (pin "K") (pinfunction "C_K") (pintype "passive"))
      (node (ref "LED44") (pin "K") (pinfunction "C_K") (pintype "passive"))
      (node (ref "LED45") (pin "K") (pinfunction "C_K") (pintype "passive"))
      (node (ref "LED46") (pin "K") (pinfunction "C_K") (pintype "passive"))
      (node (ref "LED47") (pin "K") (pinfunction "C_K") (pintype "passive"))
      (node (ref "LED48") (pin "K") (pinfunction "C_K") (pintype "passive"))
    )
    (net (code "55") (name "Net-(LED41-PadA)") (class "Default")
      (node (ref "LED41") (pin "A") (pinfunction "A_A") (pintype "passive"))
      (node (ref "R81") (pin "1") (pinfunction "1_1") (pintype "passive"))
    )
    (net (code "56") (name "Net-(LED42-PadA)") (class "Default")
      (node (ref "LED42") (pin "A") (pinfunction "A_A") (pintype "passive"))
      (node (ref "R83") (pin "1") (pinfunction "1_1") (pintype "passive"))
    )
    (net (code "57") (name "Net-(LED43-PadA)") (class "Default")
      (node (ref "LED43") (pin "A") (pinfunction "A_A") (pintype "passive"))
      (node (ref "R84") (pin "1") (pinfunction "1_1") (pintype "passive"))
    )
    (net (code "58") (name "Net-(LED44-PadA)") (class "Default")
      (node (ref "LED44") (pin "A") (pinfunction "A_A") (pintype "passive"))
      (node (ref "R85") (pin "1") (pinfunction "1_1") (pintype "passive"))
    )
    (net (code "59") (name "Net-(LED45-PadA)") (class "Default")
      (node (ref "LED45") (pin "A") (pinfunction "A_A") (pintype "passive"))
      (node (ref "R86") (pin "1") (pinfunction "1_1") (pintype "passive"))
    )
    (net (code "60") (name "Net-(LED46-PadA)") (class "Default")
      (node (ref "LED46") (pin "A") (pinfunction "A_A") (pintype "passive"))
      (node (ref "R87") (pin "1") (pinfunction "1_1") (pintype "passive"))
    )
    (net (code "61") (name "Net-(LED47-PadA)") (class "Default")
      (node (ref "LED47") (pin "A") (pinfunction "A_A") (pintype "passive"))
      (node (ref "R88") (pin "1") (pinfunction "1_1") (pintype "passive"))
    )
    (net (code "62") (name "Net-(LED48-PadA)") (class "Default")
      (node (ref "LED48") (pin "A") (pinfunction "A_A") (pintype "passive"))
      (node (ref "R89") (pin "1") (pinfunction "1_1") (pintype "passive"))
    )
    (net (code "63") (name "Net-(LED49-C)") (class "Default")
      (node (ref "JP2") (pin "7") (pinfunction "7_7") (pintype "passive"))
      (node (ref "LED49") (pin "K") (pinfunction "C_K") (pintype "passive"))
      (node (ref "LED50") (pin "K") (pinfunction "C_K") (pintype "passive"))
      (node (ref "LED51") (pin "K") (pinfunction "C_K") (pintype "passive"))
      (node (ref "LED52") (pin "K") (pinfunction "C_K") (pintype "passive"))
      (node (ref "LED53") (pin "K") (pinfunction "C_K") (pintype "passive"))
      (node (ref "LED54") (pin "K") (pinfunction "C_K") (pintype "passive"))
      (node (ref "LED55") (pin "K") (pinfunction "C_K") (pintype "passive"))
      (node (ref "LED56") (pin "K") (pinfunction "C_K") (pintype "passive"))
    )
    (net (code "64") (name "Net-(LED49-PadA)") (class "Default")
      (node (ref "LED49") (pin "A") (pinfunction "A_A") (pintype "passive"))
      (node (ref "R97") (pin "1") (pinfunction "1_1") (pintype "passive"))
    )
    (net (code "65") (name "Net-(LED50-PadA)") (class "Default")
      (node (ref "LED50") (pin "A") (pinfunction "A_A") (pintype "passive"))
      (node (ref "R99") (pin "1") (pinfunction "1_1") (pintype "passive"))
    )
    (net (code "66") (name "Net-(LED51-PadA)") (class "Default")
      (node (ref "LED51") (pin "A") (pinfunction "A_A") (pintype "passive"))
      (node (ref "R100") (pin "1") (pinfunction "1_1") (pintype "passive"))
    )
    (net (code "67") (name "Net-(LED52-PadA)") (class "Default")
      (node (ref "LED52") (pin "A") (pinfunction "A_A") (pintype "passive"))
      (node (ref "R101") (pin "1") (pinfunction "1_1") (pintype "passive"))
    )
    (net (code "68") (name "Net-(LED53-PadA)") (class "Default")
      (node (ref "LED53") (pin "A") (pinfunction "A_A") (pintype "passive"))
      (node (ref "R102") (pin "1") (pinfunction "1_1") (pintype "passive"))
    )
    (net (code "69") (name "Net-(LED54-PadA)") (class "Default")
      (node (ref "LED54") (pin "A") (pinfunction "A_A") (pintype "passive"))
      (node (ref "R103") (pin "1") (pinfunction "1_1") (pintype "passive"))
    )
    (net (code "70") (name "Net-(LED55-PadA)") (class "Default")
      (node (ref "LED55") (pin "A") (pinfunction "A_A") (pintype "passive"))
      (node (ref "R104") (pin "1") (pinfunction "1_1") (pintype "passive"))
    )
    (net (code "71") (name "Net-(LED56-PadA)") (class "Default")
      (node (ref "LED56") (pin "A") (pinfunction "A_A") (pintype "passive"))
      (node (ref "R105") (pin "1") (pinfunction "1_1") (pintype "passive"))
    )
    (net (code "72") (name "Net-(LED57-C)") (class "Default")
      (node (ref "JP2") (pin "8") (pinfunction "8_8") (pintype "passive"))
      (node (ref "LED57") (pin "K") (pinfunction "C_K") (pintype "passive"))
      (node (ref "LED58") (pin "K") (pinfunction "C_K") (pintype "passive"))
      (node (ref "LED59") (pin "K") (pinfunction "C_K") (pintype "passive"))
      (node (ref "LED60") (pin "K") (pinfunction "C_K") (pintype "passive"))
      (node (ref "LED61") (pin "K") (pinfunction "C_K") (pintype "passive"))
      (node (ref "LED62") (pin "K") (pinfunction "C_K") (pintype "passive"))
      (node (ref "LED63") (pin "K") (pinfunction "C_K") (pintype "passive"))
      (node (ref "LED64") (pin "K") (pinfunction "C_K") (pintype "passive"))
    )
    (net (code "73") (name "Net-(LED57-PadA)") (class "Default")
      (node (ref "LED57") (pin "A") (pinfunction "A_A") (pintype "passive"))
      (node (ref "R113") (pin "1") (pinfunction "1_1") (pintype "passive"))
    )
    (net (code "74") (name "Net-(LED58-PadA)") (class "Default")
      (node (ref "LED58") (pin "A") (pinfunction "A_A") (pintype "passive"))
      (node (ref "R115") (pin "1") (pinfunction "1_1") (pintype "passive"))
    )
    (net (code "75") (name "Net-(LED59-PadA)") (class "Default")
      (node (ref "LED59") (pin "A") (pinfunction "A_A") (pintype "passive"))
      (node (ref "R116") (pin "1") (pinfunction "1_1") (pintype "passive"))
    )
    (net (code "76") (name "Net-(LED60-PadA)") (class "Default")
      (node (ref "LED60") (pin "A") (pinfunction "A_A") (pintype "passive"))
      (node (ref "R117") (pin "1") (pinfunction "1_1") (pintype "passive"))
    )
    (net (code "77") (name "Net-(LED61-PadA)") (class "Default")
      (node (ref "LED61") (pin "A") (pinfunction "A_A") (pintype "passive"))
      (node (ref "R118") (pin "1") (pinfunction "1_1") (pintype "passive"))
    )
    (net (code "78") (name "Net-(LED62-PadA)") (class "Default")
      (node (ref "LED62") (pin "A") (pinfunction "A_A") (pintype "passive"))
      (node (ref "R119") (pin "1") (pinfunction "1_1") (pintype "passive"))
    )
    (net (code "79") (name "Net-(LED63-PadA)") (class "Default")
      (node (ref "LED63") (pin "A") (pinfunction "A_A") (pintype "passive"))
      (node (ref "R120") (pin "1") (pinfunction "1_1") (pintype "passive"))
    )
    (net (code "80") (name "Net-(LED64-PadA)") (class "Default")
      (node (ref "LED64") (pin "A") (pinfunction "A_A") (pintype "passive"))
      (node (ref "R121") (pin "1") (pinfunction "1_1") (pintype "passive"))
    )
    (net (code "81") (name "Net-(R10-Pad1)") (class "Default")
      (node (ref "R10") (pin "1") (pinfunction "1_1") (pintype "passive"))
      (node (ref "R19") (pin "2") (pinfunction "2_2") (pintype "passive"))
      (node (ref "R26") (pin "2") (pinfunction "2_2") (pintype "passive"))
    )
    (net (code "82") (name "Net-(R11-Pad1)") (class "Default")
      (node (ref "R11") (pin "1") (pinfunction "1_1") (pintype "passive"))
      (node (ref "R20") (pin "2") (pinfunction "2_2") (pintype "passive"))
      (node (ref "R27") (pin "2") (pinfunction "2_2") (pintype "passive"))
    )
    (net (code "83") (name "Net-(R12-Pad1)") (class "Default")
      (node (ref "R12") (pin "1") (pinfunction "1_1") (pintype "passive"))
      (node (ref "R21") (pin "2") (pinfunction "2_2") (pintype "passive"))
      (node (ref "R28") (pin "2") (pinfunction "2_2") (pintype "passive"))
    )
    (net (code "84") (name "Net-(R13-Pad1)") (class "Default")
      (node (ref "R13") (pin "1") (pinfunction "1_1") (pintype "passive"))
      (node (ref "R22") (pin "2") (pinfunction "2_2") (pintype "passive"))
      (node (ref "R29") (pin "2") (pinfunction "2_2") (pintype "passive"))
    )
    (net (code "85") (name "Net-(R14-Pad1)") (class "Default")
      (node (ref "R14") (pin "1") (pinfunction "1_1") (pintype "passive"))
      (node (ref "R23") (pin "2") (pinfunction "2_2") (pintype "passive"))
      (node (ref "R30") (pin "2") (pinfunction "2_2") (pintype "passive"))
    )
    (net (code "86") (name "Net-(R15-Pad1)") (class "Default")
      (node (ref "R15") (pin "1") (pinfunction "1_1") (pintype "passive"))
      (node (ref "R24") (pin "2") (pinfunction "2_2") (pintype "passive"))
      (node (ref "R31") (pin "2") (pinfunction "2_2") (pintype "passive"))
    )
    (net (code "87") (name "Net-(R17-Pad2)") (class "Default")
      (node (ref "R17") (pin "2") (pinfunction "2_2") (pintype "passive"))
      (node (ref "R18") (pin "2") (pinfunction "2_2") (pintype "passive"))
      (node (ref "R2") (pin "1") (pinfunction "1_1") (pintype "passive"))
    )
    (net (code "88") (name "Net-(R18-Pad1)") (class "Default")
      (node (ref "R18") (pin "1") (pinfunction "1_1") (pintype "passive"))
      (node (ref "R33") (pin "2") (pinfunction "2_2") (pintype "passive"))
      (node (ref "R34") (pin "2") (pinfunction "2_2") (pintype "passive"))
    )
    (net (code "89") (name "Net-(R26-Pad1)") (class "Default")
      (node (ref "R26") (pin "1") (pinfunction "1_1") (pintype "passive"))
      (node (ref "R35") (pin "2") (pinfunction "2_2") (pintype "passive"))
      (node (ref "R42") (pin "2") (pinfunction "2_2") (pintype "passive"))
    )
    (net (code "90") (name "Net-(R27-Pad1)") (class "Default")
      (node (ref "R27") (pin "1") (pinfunction "1_1") (pintype "passive"))
      (node (ref "R36") (pin "2") (pinfunction "2_2") (pintype "passive"))
      (node (ref "R43") (pin "2") (pinfunction "2_2") (pintype "passive"))
    )
    (net (code "91") (name "Net-(R28-Pad1)") (class "Default")
      (node (ref "R28") (pin "1") (pinfunction "1_1") (pintype "passive"))
      (node (ref "R37") (pin "2") (pinfunction "2_2") (pintype "passive"))
      (node (ref "R44") (pin "2") (pinfunction "2_2") (pintype "passive"))
    )
    (net (code "92") (name "Net-(R29-Pad1)") (class "Default")
      (node (ref "R29") (pin "1") (pinfunction "1_1") (pintype "passive"))
      (node (ref "R38") (pin "2") (pinfunction "2_2") (pintype "passive"))
      (node (ref "R45") (pin "2") (pinfunction "2_2") (pintype "passive"))
    )
    (net (code "93") (name "Net-(R30-Pad1)") (class "Default")
      (node (ref "R30") (pin "1") (pinfunction "1_1") (pintype "passive"))
      (node (ref "R39") (pin "2") (pinfunction "2_2") (pintype "passive"))
      (node (ref "R46") (pin "2") (pinfunction "2_2") (pintype "passive"))
    )
    (net (code "94") (name "Net-(R31-Pad1)") (class "Default")
      (node (ref "R31") (pin "1") (pinfunction "1_1") (pintype "passive"))
      (node (ref "R40") (pin "2") (pinfunction "2_2") (pintype "passive"))
      (node (ref "R47") (pin "2") (pinfunction "2_2") (pintype "passive"))
    )
    (net (code "95") (name "Net-(R34-Pad1)") (class "Default")
      (node (ref "R34") (pin "1") (pinfunction "1_1") (pintype "passive"))
      (node (ref "R49") (pin "2") (pinfunction "2_2") (pintype "passive"))
      (node (ref "R50") (pin "2") (pinfunction "2_2") (pintype "passive"))
    )
    (net (code "96") (name "Net-(R42-Pad1)") (class "Default")
      (node (ref "R42") (pin "1") (pinfunction "1_1") (pintype "passive"))
      (node (ref "R51") (pin "2") (pinfunction "2_2") (pintype "passive"))
      (node (ref "R58") (pin "2") (pinfunction "2_2") (pintype "passive"))
    )
    (net (code "97") (name "Net-(R43-Pad1)") (class "Default")
      (node (ref "R43") (pin "1") (pinfunction "1_1") (pintype "passive"))
      (node (ref "R52") (pin "2") (pinfunction "2_2") (pintype "passive"))
      (node (ref "R59") (pin "2") (pinfunction "2_2") (pintype "passive"))
    )
    (net (code "98") (name "Net-(R44-Pad1)") (class "Default")
      (node (ref "R44") (pin "1") (pinfunction "1_1") (pintype "passive"))
      (node (ref "R53") (pin "2") (pinfunction "2_2") (pintype "passive"))
      (node (ref "R60") (pin "2") (pinfunction "2_2") (pintype "passive"))
    )
    (net (code "99") (name "Net-(R45-Pad1)") (class "Default")
      (node (ref "R45") (pin "1") (pinfunction "1_1") (pintype "passive"))
      (node (ref "R54") (pin "2") (pinfunction "2_2") (pintype "passive"))
      (node (ref "R61") (pin "2") (pinfunction "2_2") (pintype "passive"))
    )
    (net (code "100") (name "Net-(R46-Pad1)") (class "Default")
      (node (ref "R46") (pin "1") (pinfunction "1_1") (pintype "passive"))
      (node (ref "R55") (pin "2") (pinfunction "2_2") (pintype "passive"))
      (node (ref "R62") (pin "2") (pinfunction "2_2") (pintype "passive"))
    )
    (net (code "101") (name "Net-(R47-Pad1)") (class "Default")
      (node (ref "R47") (pin "1") (pinfunction "1_1") (pintype "passive"))
      (node (ref "R56") (pin "2") (pinfunction "2_2") (pintype "passive"))
      (node (ref "R63") (pin "2") (pinfunction "2_2") (pintype "passive"))
    )
    (net (code "102") (name "Net-(R50-Pad1)") (class "Default")
      (node (ref "R50") (pin "1") (pinfunction "1_1") (pintype "passive"))
      (node (ref "R65") (pin "2") (pinfunction "2_2") (pintype "passive"))
      (node (ref "R66") (pin "2") (pinfunction "2_2") (pintype "passive"))
    )
    (net (code "103") (name "Net-(R58-Pad1)") (class "Default")
      (node (ref "R58") (pin "1") (pinfunction "1_1") (pintype "passive"))
      (node (ref "R67") (pin "2") (pinfunction "2_2") (pintype "passive"))
      (node (ref "R74") (pin "2") (pinfunction "2_2") (pintype "passive"))
    )
    (net (code "104") (name "Net-(R59-Pad1)") (class "Default")
      (node (ref "R59") (pin "1") (pinfunction "1_1") (pintype "passive"))
      (node (ref "R68") (pin "2") (pinfunction "2_2") (pintype "passive"))
      (node (ref "R75") (pin "2") (pinfunction "2_2") (pintype "passive"))
    )
    (net (code "105") (name "Net-(R60-Pad1)") (class "Default")
      (node (ref "R60") (pin "1") (pinfunction "1_1") (pintype "passive"))
      (node (ref "R69") (pin "2") (pinfunction "2_2") (pintype "passive"))
      (node (ref "R76") (pin "2") (pinfunction "2_2") (pintype "passive"))
    )
    (net (code "106") (name "Net-(R61-Pad1)") (class "Default")
      (node (ref "R61") (pin "1") (pinfunction "1_1") (pintype "passive"))
      (node (ref "R70") (pin "2") (pinfunction "2_2") (pintype "passive"))
      (node (ref "R77") (pin "2") (pinfunction "2_2") (pintype "passive"))
    )
    (net (code "107") (name "Net-(R62-Pad1)") (class "Default")
      (node (ref "R62") (pin "1") (pinfunction "1_1") (pintype "passive"))
      (node (ref "R71") (pin "2") (pinfunction "2_2") (pintype "passive"))
      (node (ref "R78") (pin "2") (pinfunction "2_2") (pintype "passive"))
    )
    (net (code "108") (name "Net-(R63-Pad1)") (class "Default")
      (node (ref "R63") (pin "1") (pinfunction "1_1") (pintype "passive"))
      (node (ref "R72") (pin "2") (pinfunction "2_2") (pintype "passive"))
      (node (ref "R79") (pin "2") (pinfunction "2_2") (pintype "passive"))
    )
    (net (code "109") (name "Net-(R66-Pad1)") (class "Default")
      (node (ref "R66") (pin "1") (pinfunction "1_1") (pintype "passive"))
      (node (ref "R81") (pin "2") (pinfunction "2_2") (pintype "passive"))
      (node (ref "R82") (pin "2") (pinfunction "2_2") (pintype "passive"))
    )
    (net (code "110") (name "Net-(R74-Pad1)") (class "Default")
      (node (ref "R74") (pin "1") (pinfunction "1_1") (pintype "passive"))
      (node (ref "R83") (pin "2") (pinfunction "2_2") (pintype "passive"))
      (node (ref "R90") (pin "2") (pinfunction "2_2") (pintype "passive"))
    )
    (net (code "111") (name "Net-(R75-Pad1)") (class "Default")
      (node (ref "R75") (pin "1") (pinfunction "1_1") (pintype "passive"))
      (node (ref "R84") (pin "2") (pinfunction "2_2") (pintype "passive"))
      (node (ref "R91") (pin "2") (pinfunction "2_2") (pintype "passive"))
    )
    (net (code "112") (name "Net-(R76-Pad1)") (class "Default")
      (node (ref "R76") (pin "1") (pinfunction "1_1") (pintype "passive"))
      (node (ref "R85") (pin "2") (pinfunction "2_2") (pintype "passive"))
      (node (ref "R92") (pin "2") (pinfunction "2_2") (pintype "passive"))
    )
    (net (code "113") (name "Net-(R77-Pad1)") (class "Default")
      (node (ref "R77") (pin "1") (pinfunction "1_1") (pintype "passive"))
      (node (ref "R86") (pin "2") (pinfunction "2_2") (pintype "passive"))
      (node (ref "R93") (pin "2") (pinfunction "2_2") (pintype "passive"))
    )
    (net (code "114") (name "Net-(R78-Pad1)") (class "Default")
      (node (ref "R78") (pin "1") (pinfunction "1_1") (pintype "passive"))
      (node (ref "R87") (pin "2") (pinfunction "2_2") (pintype "passive"))
      (node (ref "R94") (pin "2") (pinfunction "2_2") (pintype "passive"))
    )
    (net (code "115") (name "Net-(R79-Pad1)") (class "Default")
      (node (ref "R79") (pin "1") (pinfunction "1_1") (pintype "passive"))
      (node (ref "R88") (pin "2") (pinfunction "2_2") (pintype "passive"))
      (node (ref "R95") (pin "2") (pinfunction "2_2") (pintype "passive"))
    )
    (net (code "116") (name "Net-(R82-Pad1)") (class "Default")
      (node (ref "R82") (pin "1") (pinfunction "1_1") (pintype "passive"))
      (node (ref "R97") (pin "2") (pinfunction "2_2") (pintype "passive"))
      (node (ref "R98") (pin "2") (pinfunction "2_2") (pintype "passive"))
    )
    (net (code "117") (name "Net-(R100-Pad2)") (class "Default")
      (node (ref "R100") (pin "2") (pinfunction "2_2") (pintype "passive"))
      (node (ref "R107") (pin "2") (pinfunction "2_2") (pintype "passive"))
      (node (ref "R91") (pin "1") (pinfunction "1_1") (pintype "passive"))
    )
    (net (code "118") (name "Net-(R101-Pad2)") (class "Default")
      (node (ref "R101") (pin "2") (pinfunction "2_2") (pintype "passive"))
      (node (ref "R108") (pin "2") (pinfunction "2_2") (pintype "passive"))
      (node (ref "R92") (pin "1") (pinfunction "1_1") (pintype "passive"))
    )
    (net (code "119") (name "Net-(R102-Pad2)") (class "Default")
      (node (ref "R102") (pin "2") (pinfunction "2_2") (pintype "passive"))
      (node (ref "R109") (pin "2") (pinfunction "2_2") (pintype "passive"))
      (node (ref "R93") (pin "1") (pinfunction "1_1") (pintype "passive"))
    )
    (net (code "120") (name "Net-(R103-Pad2)") (class "Default")
      (node (ref "R103") (pin "2") (pinfunction "2_2") (pintype "passive"))
      (node (ref "R110") (pin "2") (pinfunction "2_2") (pintype "passive"))
      (node (ref "R94") (pin "1") (pinfunction "1_1") (pintype "passive"))
    )
    (net (code "121") (name "Net-(R104-Pad2)") (class "Default")
      (node (ref "R104") (pin "2") (pinfunction "2_2") (pintype "passive"))
      (node (ref "R111") (pin "2") (pinfunction "2_2") (pintype "passive"))
      (node (ref "R95") (pin "1") (pinfunction "1_1") (pintype "passive"))
    )
    (net (code "122") (name "Net-(R106-Pad1)") (class "Default")
      (node (ref "R106") (pin "1") (pinfunction "1_1") (pintype "passive"))
      (node (ref "R115") (pin "2") (pinfunction "2_2") (pintype "passive"))
    )
    (net (code "123") (name "Net-(R106-Pad2)") (class "Default")
      (node (ref "R106") (pin "2") (pinfunction "2_2") (pintype "passive"))
      (node (ref "R90") (pin "1") (pinfunction "1_1") (pintype "passive"))
      (node (ref "R99") (pin "2") (pinfunction "2_2") (pintype "passive"))
    )
    (net (code "124") (name "Net-(R107-Pad1)") (class "Default")
      (node (ref "R107") (pin "1") (pinfunction "1_1") (pintype "passive"))
      (node (ref "R116") (pin "2") (pinfunction "2_2") (pintype "passive"))
    )
    (net (code "125") (name "Net-(R108-Pad1)") (class "Default")
      (node (ref "R108") (pin "1") (pinfunction "1_1") (pintype "passive"))
      (node (ref "R117") (pin "2") (pinfunction "2_2") (pintype "passive"))
    )
    (net (code "126") (name "Net-(R109-Pad1)") (class "Default")
      (node (ref "R109") (pin "1") (pinfunction "1_1") (pintype "passive"))
      (node (ref "R118") (pin "2") (pinfunction "2_2") (pintype "passive"))
    )
    (net (code "127") (name "Net-(R110-Pad1)") (class "Default")
      (node (ref "R110") (pin "1") (pinfunction "1_1") (pintype "passive"))
      (node (ref "R119") (pin "2") (pinfunction "2_2") (pintype "passive"))
    )
    (net (code "128") (name "Net-(R111-Pad1)") (class "Default")
      (node (ref "R111") (pin "1") (pinfunction "1_1") (pintype "passive"))
      (node (ref "R120") (pin "2") (pinfunction "2_2") (pintype "passive"))
    )
    (net (code "129") (name "Net-(R113-Pad2)") (class "Default")
      (node (ref "R113") (pin "2") (pinfunction "2_2") (pintype "passive"))
      (node (ref "R98") (pin "1") (pinfunction "1_1") (pintype "passive"))
    )
  )
)
